# Sheet1.net
KiCad netlist of a schematic drawn in Altium Designer
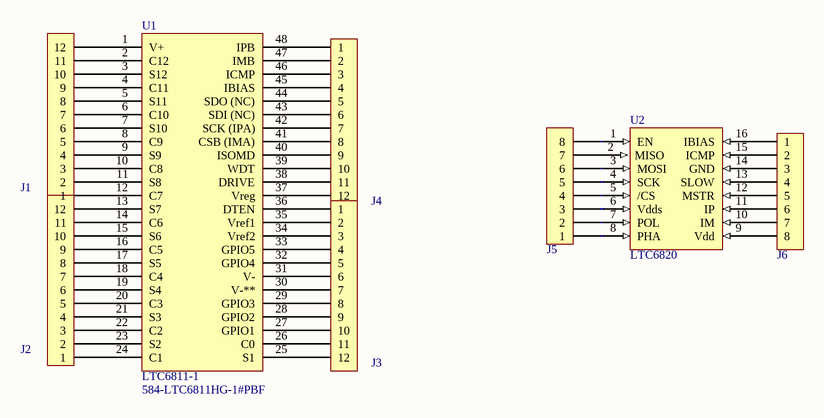
[diagram p0: Sheet1.SchDoc]

(export (version "E")
  (design (tool "Eeschema 10.0.6"))
  (components
    (comp (ref "J1")
      (value "61301211121")
      (footprint "J_Pinheader_1x12")
      (description "THT Vertical Pin Header WR-PHD, Pitch 2.54 mm, Single Row, 12 pins")
      (libsource (lib "") (part "J_Pinheader_1x12_1"))
    )
    (comp (ref "J2")
      (value "61301211121")
      (footprint "J_Pinheader_1x12")
      (description "THT Vertical Pin Header WR-PHD, Pitch 2.54 mm, Single Row, 12 pins")
      (libsource (lib "") (part "J_Pinheader_1x12_1"))
    )
    (comp (ref "J3")
      (value "61301211121")
      (footprint "J_Pinheader_1x12")
      (description "THT Vertical Pin Header WR-PHD, Pitch 2.54 mm, Single Row, 12 pins")
      (libsource (lib "Electromechanical") (part "J_Pinheader_1x12"))
    )
    (comp (ref "J4")
      (value "61301211121")
      (footprint "J_Pinheader_1x12")
      (description "THT Vertical Pin Header WR-PHD, Pitch 2.54 mm, Single Row, 12 pins")
      (libsource (lib "Electromechanical") (part "J_Pinheader_1x12"))
    )
    (comp (ref "J5")
      (value "61301211121")
      (footprint "J_Pinheader_1x8")
      (description "THT Vertical Pin Header WR-PHD, Pitch 2.54 mm, Single Row, 12 pins")
      (libsource (lib "Electromechanical") (part "J_Pinheader_1x8"))
    )
    (comp (ref "J6")
      (value "61301211121")
      (footprint "J_Pinheader_1x8")
      (description "THT Vertical Pin Header WR-PHD, Pitch 2.54 mm, Single Row, 12 pins")
      (libsource (lib "") (part "J_Pinheader_1x8_1"))
    )
    (comp (ref "U1")
      (value "LTC6811-1")
      (footprint "U_LTC6811G-2")
      (description "12 Channel Multicell Battery Monitor with Daisy Chain Interface, Generation 4")
      (fields
        (field (name "MANUFACTURER") "Analog Devices / Linear Technology")
        (field (name "MANUFACTURER PART NUMBER") "LTC6811HG-1#PBF")
        (field (name "MANUFACTURER PART NUMBER 1") "LTC6811-1")
        (field (name "SUPPLIER PART NUMBER 2") "584-LTC6811HG-1#PBF")
        (field (name ".CREATOR") "GP")
      )
      (libsource (lib "Integrated circuits") (part "U_LTC6811-1"))
    )
    (comp (ref "U2")
      (value "LTC6820")
      (footprint "LTC6820")
      (libsource (lib "Integrated circuits") (part "U_LTC6820"))
    )
  )
  (nets
    (net (code "1") (name "Net-(U1-C0)") (class "Default")
      (node (ref "J3") (pin "11") (pinfunction "11_11") (pintype "passive"))
      (node (ref "U1") (pin "26") (pinfunction "C0_26") (pintype "passive"))
    )
    (net (code "2") (name "Net-(U1-C1)") (class "Default")
      (node (ref "J2") (pin "1") (pinfunction "1_1") (pintype "passive"))
      (node (ref "U1") (pin "24") (pinfunction "C1_24") (pintype "passive"))
    )
    (net (code "3") (name "Net-(U1-C2)") (class "Default")
      (node (ref "J2") (pin "3") (pinfunction "3_3") (pintype "passive"))
      (node (ref "U1") (pin "22") (pinfunction "C2_22") (pintype "passive"))
    )
    (net (code "4") (name "Net-(U1-C3)") (class "Default")
      (node (ref "J2") (pin "5") (pinfunction "5_5") (pintype "passive"))
      (node (ref "U1") (pin "20") (pinfunction "C3_20") (pintype "passive"))
    )
    (net (code "5") (name "Net-(U1-C4)") (class "Default")
      (node (ref "J2") (pin "7") (pinfunction "7_7") (pintype "passive"))
      (node (ref "U1") (pin "18") (pinfunction "C4_18") (pintype "passive"))
    )
    (net (code "6") (name "Net-(U1-C5)") (class "Default")
      (node (ref "J2") (pin "9") (pinfunction "9_9") (pintype "passive"))
      (node (ref "U1") (pin "16") (pinfunction "C5_16") (pintype "passive"))
    )
    (net (code "7") (name "Net-(U1-C6)") (class "Default")
      (node (ref "J2") (pin "11") (pinfunction "11_11") (pintype "passive"))
      (node (ref "U1") (pin "14") (pinfunction "C6_14") (pintype "passive"))
    )
    (net (code "8") (name "Net-(U1-C7)") (class "Default")
      (node (ref "J1") (pin "1") (pinfunction "1_1") (pintype "passive"))
      (node (ref "U1") (pin "12") (pinfunction "C7_12") (pintype "passive"))
    )
    (net (code "9") (name "Net-(U1-C8)") (class "Default")
      (node (ref "J1") (pin "3") (pinfunction "3_3") (pintype "passive"))
      (node (ref "U1") (pin "10") (pinfunction "C8_10") (pintype "passive"))
    )
    (net (code "10") (name "Net-(U1-C9)") (class "Default")
      (node (ref "J1") (pin "5") (pinfunction "5_5") (pintype "passive"))
      (node (ref "U1") (pin "8") (pinfunction "C9_8") (pintype "passive"))
    )
    (net (code "11") (name "Net-(U1-C10)") (class "Default")
      (node (ref "J1") (pin "7") (pinfunction "7_7") (pintype "passive"))
      (node (ref "U1") (pin "6") (pinfunction "C10_6") (pintype "passive"))
    )
    (net (code "12") (name "Net-(U1-C11)") (class "Default")
      (node (ref "J1") (pin "9") (pinfunction "9_9") (pintype "passive"))
      (node (ref "U1") (pin "4") (pinfunction "C11_4") (pintype "passive"))
    )
    (net (code "13") (name "Net-(U1-C12)") (class "Default")
      (node (ref "J1") (pin "11") (pinfunction "11_11") (pintype "passive"))
      (node (ref "U1") (pin "2") (pinfunction "C12_2") (pintype "passive"))
    )
    (net (code "14") (name "Net-(U1-CSB_(IMA))") (class "Default")
      (node (ref "J4") (pin "8") (pinfunction "8_8") (pintype "passive"))
      (node (ref "U1") (pin "41") (pinfunction "CSB_(IMA)_41") (pintype "passive"))
    )
    (net (code "15") (name "Net-(U1-DRIVE)") (class "Default")
      (node (ref "J4") (pin "11") (pinfunction "11_11") (pintype "passive"))
      (node (ref "U1") (pin "38") (pinfunction "DRIVE_38") (pintype "passive"))
    )
    (net (code "16") (name "Net-(U1-DTEN)") (class "Default")
      (node (ref "J3") (pin "1") (pinfunction "1_1") (pintype "passive"))
      (node (ref "U1") (pin "36") (pinfunction "DTEN_36") (pintype "passive"))
    )
    (net (code "17") (name "Net-(U1-GPIO1)") (class "Default")
      (node (ref "J3") (pin "10") (pinfunction "10_10") (pintype "passive"))
      (node (ref "U1") (pin "27") (pinfunction "GPIO1_27") (pintype "passive"))
    )
    (net (code "18") (name "Net-(U1-GPIO2)") (class "Default")
      (node (ref "J3") (pin "9") (pinfunction "9_9") (pintype "passive"))
      (node (ref "U1") (pin "28") (pinfunction "GPIO2_28") (pintype "passive"))
    )
    (net (code "19") (name "Net-(U1-GPIO3)") (class "Default")
      (node (ref "J3") (pin "8") (pinfunction "8_8") (pintype "passive"))
      (node (ref "U1") (pin "29") (pinfunction "GPIO3_29") (pintype "passive"))
    )
    (net (code "20") (name "Net-(U1-GPIO4)") (class "Default")
      (node (ref "J3") (pin "5") (pinfunction "5_5") (pintype "passive"))
      (node (ref "U1") (pin "32") (pinfunction "GPIO4_32") (pintype "passive"))
    )
    (net (code "21") (name "Net-(U1-GPIO5)") (class "Default")
      (node (ref "J3") (pin "4") (pinfunction "4_4") (pintype "passive"))
      (node (ref "U1") (pin "33") (pinfunction "GPIO5_33") (pintype "passive"))
    )
    (net (code "22") (name "Net-(U1-IBIAS)") (class "Default")
      (node (ref "J4") (pin "4") (pinfunction "4_4") (pintype "passive"))
      (node (ref "U1") (pin "45") (pinfunction "IBIAS_45") (pintype "passive"))
    )
    (net (code "23") (name "Net-(U1-ICMP)") (class "Default")
      (node (ref "J4") (pin "3") (pinfunction "3_3") (pintype "passive"))
      (node (ref "U1") (pin "46") (pinfunction "ICMP_46") (pintype "passive"))
    )
    (net (code "24") (name "Net-(U1-IMB)") (class "Default")
      (node (ref "J4") (pin "2") (pinfunction "2_2") (pintype "passive"))
      (node (ref "U1") (pin "47") (pinfunction "IMB_47") (pintype "passive"))
    )
    (net (code "25") (name "Net-(U1-IPB)") (class "Default")
      (node (ref "J4") (pin "1") (pinfunction "1_1") (pintype "passive"))
      (node (ref "U1") (pin "48") (pinfunction "IPB_48") (pintype "passive"))
    )
    (net (code "26") (name "Net-(U1-ISOMD)") (class "Default")
      (node (ref "J4") (pin "9") (pinfunction "9_9") (pintype "passive"))
      (node (ref "U1") (pin "40") (pinfunction "ISOMD_40") (pintype "passive"))
    )
    (net (code "27") (name "Net-(U1-S1)") (class "Default")
      (node (ref "J3") (pin "12") (pinfunction "12_12") (pintype "passive"))
      (node (ref "U1") (pin "25") (pinfunction "S1_25") (pintype "passive"))
    )
    (net (code "28") (name "Net-(U1-S2)") (class "Default")
      (node (ref "J2") (pin "2") (pinfunction "2_2") (pintype "passive"))
      (node (ref "U1") (pin "23") (pinfunction "S2_23") (pintype "passive"))
    )
    (net (code "29") (name "Net-(U1-S3)") (class "Default")
      (node (ref "J2") (pin "4") (pinfunction "4_4") (pintype "passive"))
      (node (ref "U1") (pin "21") (pinfunction "S3_21") (pintype "passive"))
    )
    (net (code "30") (name "Net-(U1-S4)") (class "Default")
      (node (ref "J2") (pin "6") (pinfunction "6_6") (pintype "passive"))
      (node (ref "U1") (pin "19") (pinfunction "S4_19") (pintype "passive"))
    )
    (net (code "31") (name "Net-(U1-S5)") (class "Default")
      (node (ref "J2") (pin "8") (pinfunction "8_8") (pintype "passive"))
      (node (ref "U1") (pin "17") (pinfunction "S5_17") (pintype "passive"))
    )
    (net (code "32") (name "Net-(U1-S6)") (class "Default")
      (node (ref "J2") (pin "10") (pinfunction "10_10") (pintype "passive"))
      (node (ref "U1") (pin "15") (pinfunction "S6_15") (pintype "passive"))
    )
    (net (code "33") (name "Net-(U1-S7)") (class "Default")
      (node (ref "J2") (pin "12") (pinfunction "12_12") (pintype "passive"))
      (node (ref "U1") (pin "13") (pinfunction "S7_13") (pintype "passive"))
    )
    (net (code "34") (name "Net-(U1-S8)") (class "Default")
      (node (ref "J1") (pin "2") (pinfunction "2_2") (pintype "passive"))
      (node (ref "U1") (pin "11") (pinfunction "S8_11") (pintype "passive"))
    )
    (net (code "35") (name "Net-(U1-S9)") (class "Default")
      (node (ref "J1") (pin "4") (pinfunction "4_4") (pintype "passive"))
      (node (ref "U1") (pin "9") (pinfunction "S9_9") (pintype "passive"))
    )
    (net (code "36") (name "Net-(U1-S10)") (class "Default")
      (node (ref "J1") (pin "6") (pinfunction "6_6") (pintype "passive"))
      (node (ref "U1") (pin "7") (pinfunction "S10_7") (pintype "passive"))
    )
    (net (code "37") (name "Net-(U1-S11)") (class "Default")
      (node (ref "J1") (pin "8") (pinfunction "8_8") (pintype "passive"))
      (node (ref "U1") (pin "5") (pinfunction "S11_5") (pintype "passive"))
    )
    (net (code "38") (name "Net-(U1-S12)") (class "Default")
      (node (ref "J1") (pin "10") (pinfunction "10_10") (pintype "passive"))
      (node (ref "U1") (pin "3") (pinfunction "S12_3") (pintype "passive"))
    )
    (net (code "39") (name "Net-(U1-SCK_(IPA))") (class "Default")
      (node (ref "J4") (pin "7") (pinfunction "7_7") (pintype "passive"))
      (node (ref "U1") (pin "42") (pinfunction "SCK_(IPA)_42") (pintype "passive"))
    )
    (net (code "40") (name "Net-(U1-SDI_(NC))") (class "Default")
      (node (ref "J4") (pin "6") (pinfunction "6_6") (pintype "passive"))
      (node (ref "U1") (pin "43") (pinfunction "SDI_(NC)_43") (pintype "passive"))
    )
    (net (code "41") (name "Net-(U1-SDO_(NC))") (class "Default")
      (node (ref "J4") (pin "5") (pinfunction "5_5") (pintype "passive"))
      (node (ref "U1") (pin "44") (pinfunction "SDO_(NC)_44") (pintype "passive"))
    )
    (net (code "42") (name "Net-(U1-V+)") (class "Default")
      (node (ref "J1") (pin "12") (pinfunction "12_12") (pintype "passive"))
      (node (ref "U1") (pin "1") (pinfunction "V+_1") (pintype "passive"))
    )
    (net (code "43") (name "Net-(U1-V-)") (class "Default")
      (node (ref "J3") (pin "6") (pinfunction "6_6") (pintype "passive"))
      (node (ref "U1") (pin "31") (pinfunction "V-_31") (pintype "passive"))
    )
    (net (code "44") (name "Net-(U1-V-**)") (class "Default")
      (node (ref "J3") (pin "7") (pinfunction "7_7") (pintype "passive"))
      (node (ref "U1") (pin "30") (pinfunction "V-**_30") (pintype "passive"))
    )
    (net (code "45") (name "Net-(U1-Vref1)") (class "Default")
      (node (ref "J3") (pin "2") (pinfunction "2_2") (pintype "passive"))
      (node (ref "U1") (pin "35") (pinfunction "Vref1_35") (pintype "passive"))
    )
    (net (code "46") (name "Net-(U1-Vref2)") (class "Default")
      (node (ref "J3") (pin "3") (pinfunction "3_3") (pintype "passive"))
      (node (ref "U1") (pin "34") (pinfunction "Vref2_34") (pintype "passive"))
    )
    (net (code "47") (name "Net-(U1-Vreg)") (class "Default")
      (node (ref "J4") (pin "12") (pinfunction "12_12") (pintype "passive"))
      (node (ref "U1") (pin "37") (pinfunction "Vreg_37") (pintype "passive"))
    )
    (net (code "48") (name "Net-(U1-WDT)") (class "Default")
      (node (ref "J4") (pin "10") (pinfunction "10_10") (pintype "passive"))
      (node (ref "U1") (pin "39") (pinfunction "WDT_39") (pintype "passive"))
    )
    (net (code "49") (name "Net-(U2-EN)") (class "Default")
      (node (ref "J5") (pin "8") (pinfunction "8_8") (pintype "passive"))
      (node (ref "U2") (pin "1") (pinfunction "EN_1") (pintype "input"))
    )
    (net (code "50") (name "Net-(U2-GND)") (class "Default")
      (node (ref "J6") (pin "3") (pinfunction "3_3") (pintype "passive"))
      (node (ref "U2") (pin "14") (pinfunction "GND_14") (pintype "input"))
    )
    (net (code "51") (name "Net-(U2-IBIAS)") (class "Default")
      (node (ref "J6") (pin "1") (pinfunction "1_1") (pintype "passive"))
      (node (ref "U2") (pin "16") (pinfunction "IBIAS_16") (pintype "input"))
    )
    (net (code "52") (name "Net-(U2-ICMP)") (class "Default")
      (node (ref "J6") (pin "2") (pinfunction "2_2") (pintype "passive"))
      (node (ref "U2") (pin "15") (pinfunction "ICMP_15") (pintype "input"))
    )
    (net (code "53") (name "Net-(U2-IM)") (class "Default")
      (node (ref "J6") (pin "7") (pinfunction "7_7") (pintype "passive"))
      (node (ref "U2") (pin "10") (pinfunction "IM_10") (pintype "input"))
    )
    (net (code "54") (name "Net-(U2-IP)") (class "Default")
      (node (ref "J6") (pin "6") (pinfunction "6_6") (pintype "passive"))
      (node (ref "U2") (pin "11") (pinfunction "IP_11") (pintype "input"))
    )
    (net (code "55") (name "Net-(U2-MISO)") (class "Default")
      (node (ref "J5") (pin "7") (pinfunction "7_7") (pintype "passive"))
      (node (ref "U2") (pin "2") (pinfunction "MISO_2") (pintype "input"))
    )
    (net (code "56") (name "Net-(U2-MOSI)") (class "Default")
      (node (ref "J5") (pin "6") (pinfunction "6_6") (pintype "passive"))
      (node (ref "U2") (pin "3") (pinfunction "MOSI_3") (pintype "input"))
    )
    (net (code "57") (name "Net-(U2-MSTR)") (class "Default")
      (node (ref "J6") (pin "5") (pinfunction "5_5") (pintype "passive"))
      (node (ref "U2") (pin "12") (pinfunction "MSTR_12") (pintype "input"))
    )
    (net (code "58") (name "Net-(U2-PHA)") (class "Default")
      (node (ref "J5") (pin "1") (pinfunction "1_1") (pintype "passive"))
      (node (ref "U2") (pin "8") (pinfunction "PHA_8") (pintype "input"))
    )
    (net (code "59") (name "Net-(U2-POL)") (class "Default")
      (node (ref "J5") (pin "2") (pinfunction "2_2") (pintype "passive"))
      (node (ref "U2") (pin "7") (pinfunction "POL_7") (pintype "input"))
    )
    (net (code "60") (name "Net-(U2-SCK)") (class "Default")
      (node (ref "J5") (pin "5") (pinfunction "5_5") (pintype "passive"))
      (node (ref "U2") (pin "4") (pinfunction "SCK_4") (pintype "input"))
    )
    (net (code "61") (name "Net-(U2-SLOW)") (class "Default")
      (node (ref "J6") (pin "4") (pinfunction "4_4") (pintype "passive"))
      (node (ref "U2") (pin "13") (pinfunction "SLOW_13") (pintype "input"))
    )
    (net (code "62") (name "Net-(U2-Vdd)") (class "Default")
      (node (ref "J6") (pin "8") (pinfunction "8_8") (pintype "passive"))
      (node (ref "U2") (pin "9") (pinfunction "Vdd_9") (pintype "input"))
    )
    (net (code "63") (name "Net-(U2-Vdds)") (class "Default")
      (node (ref "J5") (pin "3") (pinfunction "3_3") (pintype "passive"))
      (node (ref "U2") (pin "6") (pinfunction "Vdds_6") (pintype "input"))
    )
    (net (code "64") (name "Net-(U2-{slash}CS)") (class "Default")
      (node (ref "J5") (pin "4") (pinfunction "4_4") (pintype "passive"))
      (node (ref "U2") (pin "5") (pinfunction "/CS_5") (pintype "input"))
    )
  )
)
